# Power_Dist_MCU.net
KiCad netlist of a schematic drawn in EAGLE
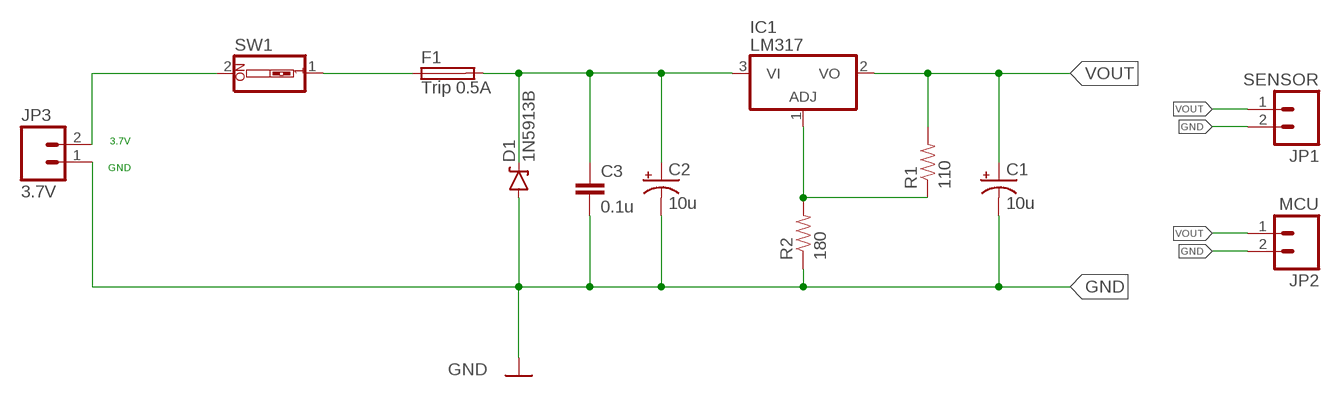
[diagram p0: schematic, sheet 1]

(export (version "E")
  (design (tool "Eeschema 10.0.6"))
  (components
    (comp (ref "C1")
      (value "10u")
      (footprint "eagle-import:CPOL-RADIAL-10UF-25V")
      (libsource (lib "eagle-import") (part "CAP_POLPTH2"))
    )
    (comp (ref "C2")
      (value "10u")
      (footprint "eagle-import:CPOL-RADIAL-10UF-25V")
      (libsource (lib "eagle-import") (part "CAP_POLPTH2"))
    )
    (comp (ref "C3")
      (value "0.1u")
      (footprint "eagle-import:CAP-PTH-SMALL")
      (libsource (lib "eagle-import") (part "CAPPTH"))
    )
    (comp (ref "D1")
      (value "1N5913B")
      (footprint "eagle-import:DIODE-BZT52")
      (libsource (lib "eagle-import") (part "DIODE-ZENER"))
    )
    (comp (ref "F1")
      (value "Trip 0.5A")
      (footprint "eagle-import:PICOFUSE")
      (libsource (lib "eagle-import") (part "PICOFUSE"))
    )
    (comp (ref "IC1")
      (value "LM317")
      (footprint "eagle-import:TO220H")
      (libsource (lib "eagle-import") (part "317T"))
    )
    (comp (ref "JP1")
      (value "SENSOR")
      (footprint "eagle-import:1X02")
      (libsource (lib "eagle-import") (part "M02PTH"))
    )
    (comp (ref "JP2")
      (value "MCU")
      (footprint "eagle-import:1X02")
      (libsource (lib "eagle-import") (part "M02PTH"))
    )
    (comp (ref "JP3")
      (value "3.7V")
      (footprint "eagle-import:JST-2-PTH")
      (libsource (lib "eagle-import") (part "M02JST-PTH-2"))
    )
    (comp (ref "R1")
      (value "110")
      (footprint "eagle-import:AXIAL-0.4")
      (libsource (lib "eagle-import") (part "RESISTORPTH-1/4W"))
    )
    (comp (ref "R2")
      (value "180")
      (footprint "eagle-import:AXIAL-0.4")
      (libsource (lib "eagle-import") (part "RESISTORPTH-1/4W"))
    )
    (comp (ref "SW1")
      (value "SW_DIP-1")
      (footprint "eagle-import:EDG-01")
      (libsource (lib "eagle-import") (part "SW_DIP-1"))
    )
  )
  (nets
    (net (code "1") (name "GND") (class "Default")
      (node (ref "C1") (pin "2") (pinfunction "-_2") (pintype "passive"))
      (node (ref "C2") (pin "2") (pinfunction "-_2") (pintype "passive"))
      (node (ref "C3") (pin "2") (pinfunction "2_2") (pintype "passive"))
      (node (ref "D1") (pin "A") (pinfunction "A_A") (pintype "passive"))
      (node (ref "JP1") (pin "2") (pinfunction "2_2") (pintype "passive"))
      (node (ref "JP2") (pin "2") (pinfunction "2_2") (pintype "passive"))
      (node (ref "JP3") (pin "1") (pinfunction "1_1") (pintype "passive"))
      (node (ref "R2") (pin "P$1") (pinfunction "1_P$1") (pintype "passive"))
    )
    (net (code "2") (name "Net-(C2-+)") (class "Default")
      (node (ref "C2") (pin "1") (pinfunction "+_1") (pintype "passive"))
      (node (ref "C3") (pin "1") (pinfunction "1_1") (pintype "passive"))
      (node (ref "D1") (pin "C") (pinfunction "C_C") (pintype "passive"))
      (node (ref "F1") (pin "2") (pinfunction "2_2") (pintype "passive"))
      (node (ref "IC1") (pin "3") (pinfunction "VI_3") (pintype "input"))
    )
    (net (code "3") (name "Net-(F1-Pad1)") (class "Default")
      (node (ref "F1") (pin "1") (pinfunction "1_1") (pintype "passive"))
      (node (ref "SW1") (pin "1") (pinfunction "1_1") (pintype "passive"))
    )
    (net (code "4") (name "Net-(IC1-ADJ)") (class "Default")
      (node (ref "IC1") (pin "1") (pinfunction "ADJ_1") (pintype "input"))
      (node (ref "R1") (pin "P$1") (pinfunction "1_P$1") (pintype "passive"))
      (node (ref "R2") (pin "P$2") (pinfunction "2_P$2") (pintype "passive"))
    )
    (net (code "5") (name "Net-(JP3-Pad2)") (class "Default")
      (node (ref "JP3") (pin "2") (pinfunction "2_2") (pintype "passive"))
      (node (ref "SW1") (pin "2") (pinfunction "2_2") (pintype "passive"))
    )
    (net (code "6") (name "VOUT") (class "Default")
      (node (ref "C1") (pin "1") (pinfunction "+_1") (pintype "passive"))
      (node (ref "IC1") (pin "2") (pinfunction "VO_2") (pintype "passive"))
      (node (ref "JP1") (pin "1") (pinfunction "1_1") (pintype "passive"))
      (node (ref "JP2") (pin "1") (pinfunction "1_1") (pintype "passive"))
      (node (ref "R1") (pin "P$2") (pinfunction "2_P$2") (pintype "passive"))
    )
  )
)
